# 12_-WIFI_Module_WF60.net
KiCad netlist of a schematic drawn in Altium Designer
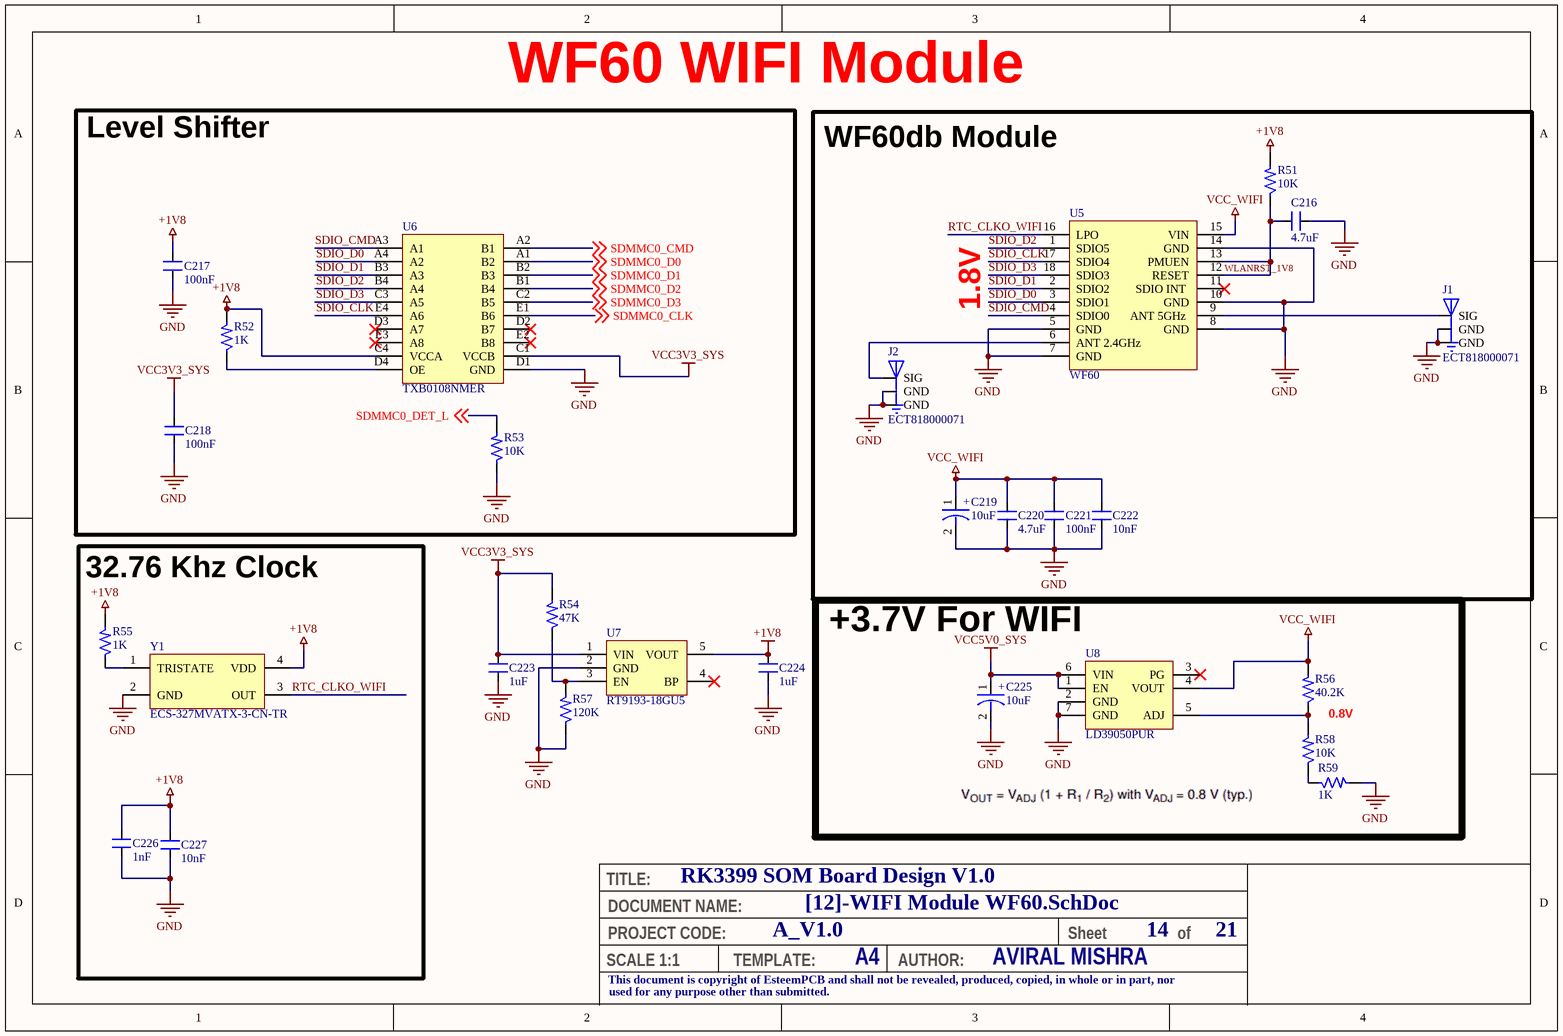
[diagram p0: [12]-WIFI Module WF60.SchDoc]

(export (version "E")
  (design (tool "Eeschema 10.0.6"))
  (components
    (comp (ref "C216")
      (value "4.7uF")
      (footprint "CAP_0402")
      (description "4.7µF ±10% 10V Ceramic Capacitor X5R 0402 (1005 Metric)")
      (fields
        (field (name "MANUFACTURER") "Samsung Electro-Mechanics")
        (field (name "MANUFACTURER PART NUMBER") "CL05A475KP5NRNC")
      )
      (libsource (lib "RK3399 _Module_Intlib") (part "CAP_4.7uF-10V-10%-0402"))
    )
    (comp (ref "C217")
      (value "100nF")
      (footprint "CAP_0402")
      (description "0.1µF ±10% 25V Ceramic Capacitor X7R 0402 (1005 Metric)")
      (fields
        (field (name "MANUFACTURER") "Walsin Technology Corporation")
        (field (name "MANUFACTURER PART NUMBER") "0402B104K250CT")
      )
      (libsource (lib "RK3399 _Module_Intlib") (part "CAP_100nF-25V-10%-0402"))
    )
    (comp (ref "C218")
      (value "100nF")
      (footprint "CAP_0402")
      (description "0.1µF ±10% 25V Ceramic Capacitor X7R 0402 (1005 Metric)")
      (fields
        (field (name "MANUFACTURER") "Walsin Technology Corporation")
        (field (name "MANUFACTURER PART NUMBER") "0402B104K250CT")
      )
      (libsource (lib "RK3399 _Module_Intlib") (part "CAP_100nF-25V-10%-0402"))
    )
    (comp (ref "C219")
      (value "10uF")
      (footprint "CAP-T_1206")
      (description "10µF Molded Tantalum Capacitors 16V 1206 (3216 Metric) 3Ohm")
      (fields
        (field (name "MANUFACTURER") "AVX Corporation")
        (field (name "MANUFACTURER PART NUMBER") "TAJA106K016SNJ")
      )
      (libsource (lib "RK3399 _Module_Intlib") (part "CAP-P_10uF-16V-10%-1206"))
    )
    (comp (ref "C220")
      (value "4.7uF")
      (footprint "CAP_0402")
      (description "4.7µF ±10% 10V Ceramic Capacitor X5R 0402 (1005 Metric)")
      (fields
        (field (name "MANUFACTURER") "Samsung Electro-Mechanics")
        (field (name "MANUFACTURER PART NUMBER") "CL05A475KP5NRNC")
      )
      (libsource (lib "RK3399 _Module_Intlib") (part "CAP_4.7uF-10V-10%-0402"))
    )
    (comp (ref "C221")
      (value "100nF")
      (footprint "CAP_0402")
      (description "0.1µF ±10% 25V Ceramic Capacitor X7R 0402 (1005 Metric)")
      (fields
        (field (name "MANUFACTURER") "Walsin Technology Corporation")
        (field (name "MANUFACTURER PART NUMBER") "0402B104K250CT")
      )
      (libsource (lib "RK3399 _Module_Intlib") (part "CAP_100nF-25V-10%-0402"))
    )
    (comp (ref "C222")
      (value "10nF")
      (footprint "CAP_0402")
      (description "10000pF ±10% 10V Ceramic Capacitor X7R 0402 (1005 Metric)")
      (fields
        (field (name "MANUFACTURER") "AVX Corporation")
        (field (name "MANUFACTURER PART NUMBER") "0402ZC103KAT2A")
      )
      (libsource (lib "RK3399 _Module_Intlib") (part "CAP_10nF-10V-10%-0402"))
    )
    (comp (ref "C223")
      (value "1uF")
      (footprint "CAP_0402")
      (description "1µF ±10% 16V Ceramic Capacitor X5R 0402 (1005 Metric)")
      (fields
        (field (name "MANUFACTURER") "Knowles Novacap")
        (field (name "MANUFACTURER PART NUMBER") "0402BW105K160YT")
      )
      (libsource (lib "RK3399 _Module_Schlib") (part "CAP_1uF-16V-10%-0402"))
    )
    (comp (ref "C224")
      (value "1uF")
      (footprint "CAP_0402")
      (description "1µF ±10% 16V Ceramic Capacitor X5R 0402 (1005 Metric)")
      (fields
        (field (name "MANUFACTURER") "Knowles Novacap")
        (field (name "MANUFACTURER PART NUMBER") "0402BW105K160YT")
      )
      (libsource (lib "RK3399 _Module_Schlib") (part "CAP_1uF-16V-10%-0402"))
    )
    (comp (ref "C225")
      (value "10uF")
      (footprint "CAP-T_1206")
      (description "10µF Molded Tantalum Capacitors 16V 1206 (3216 Metric) 3Ohm")
      (fields
        (field (name "MANUFACTURER") "AVX Corporation")
        (field (name "MANUFACTURER PART NUMBER") "TAJA106K016SNJ")
      )
      (libsource (lib "RK3399 _Module_Intlib") (part "CAP-P_10uF-16V-10%-1206"))
    )
    (comp (ref "C226")
      (value "1nF")
      (footprint "CAP_0402")
      (description "1000pF ±10% 16V Ceramic Capacitor X7R 0402 (1005 Metric)")
      (fields
        (field (name "MANUFACTURER") "Yageo")
        (field (name "MANUFACTURER PART NUMBER") "CC0402KRX7R7BB102")
      )
      (libsource (lib "RK3399 _Module_Intlib") (part "CAP_1nF-16V-10%-0402"))
    )
    (comp (ref "C227")
      (value "10nF")
      (footprint "CAP_0402")
      (description "10000pF ±10% 10V Ceramic Capacitor X7R 0402 (1005 Metric)")
      (fields
        (field (name "MANUFACTURER") "AVX Corporation")
        (field (name "MANUFACTURER PART NUMBER") "0402ZC103KAT2A")
      )
      (libsource (lib "RK3399 _Module_Intlib") (part "CAP_10nF-10V-10%-0402"))
    )
    (comp (ref "J1")
      (value "ECT818000071")
      (footprint "CON3_UFL_116_SMD_ST")
      (description "SMD RF Connectors/Coaxial Connectors RoHS")
      (fields (field (name "MANUFACTURER") "ECT"))
      (libsource (lib "RK3399 _Module_Intlib") (part "CON-PLG_3X1-ECT818000071-ST-SMD"))
    )
    (comp (ref "J2")
      (value "ECT818000071")
      (footprint "CON3_UFL_116_SMD_ST")
      (description "SMD RF Connectors/Coaxial Connectors RoHS")
      (fields (field (name "MANUFACTURER") "ECT"))
      (libsource (lib "RK3399 _Module_Intlib") (part "CON-PLG_3X1-ECT818000071-ST-SMD"))
    )
    (comp (ref "R51")
      (value "10K")
      (footprint "RES_0402")
      (description "10 kOhms ±1% 0.1W, 1/10W Chip Resistor 0402 (1005 Metric) Anti-Sulfur Thin Film")
      (fields
        (field (name "MANUFACTURER") "Vishay Beyschlag/Draloric/BC Components")
        (field (name "MANUFACTURER PART NUMBER") "MCS04020C1002FE000")
      )
      (libsource (lib "RK3399 _Module_Intlib") (part "RES_10K-0.1W-1%-0402"))
    )
    (comp (ref "R52")
      (value "1K")
      (footprint "RES_0402")
      (description "1 kOhms ±1% 0.1W, 1/10W Chip Resistor 0402 (1005 Metric) Anti-Sulfur Thin Film")
      (fields
        (field (name "MANUFACTURER") "Vishay Beyschlag/Draloric/BC Components")
        (field (name "MANUFACTURER PART NUMBER") "MCS04020C1001FE000")
      )
      (libsource (lib "RK3399 _Module_Intlib") (part "RES_1K-0.1W-1%-0402"))
    )
    (comp (ref "R53")
      (value "10K")
      (footprint "RES_0402")
      (description "10 kOhms ±1% 0.1W, 1/10W Chip Resistor 0402 (1005 Metric) Anti-Sulfur Thin Film")
      (fields
        (field (name "MANUFACTURER") "Vishay Beyschlag/Draloric/BC Components")
        (field (name "MANUFACTURER PART NUMBER") "MCS04020C1002FE000")
      )
      (libsource (lib "RK3399 _Module_Intlib") (part "RES_10K-0.1W-1%-0402"))
    )
    (comp (ref "R54")
      (value "47K")
      (footprint "RES_0402")
      (description "47 kOhms ±1% 0.1W, 1/10W Chip Resistor 0402 (1005 Metric) Automotive AEC-Q200 Thick Film")
      (fields
        (field (name "MANUFACTURER") "Panasonic Electronic Components")
        (field (name "MANUFACTURER PART NUMBER") "ERJ-2RKF4702X")
      )
      (libsource (lib "RK3399 _Module_Schlib") (part "RES_47K-0.1W-1%-0402"))
    )
    (comp (ref "R55")
      (value "1K")
      (footprint "RES_0402")
      (description "1 kOhms ±1% 0.1W, 1/10W Chip Resistor 0402 (1005 Metric) Anti-Sulfur Thin Film")
      (fields
        (field (name "MANUFACTURER") "Vishay Beyschlag/Draloric/BC Components")
        (field (name "MANUFACTURER PART NUMBER") "MCS04020C1001FE000")
      )
      (libsource (lib "RK3399 _Module_Intlib") (part "RES_1K-0.1W-1%-0402"))
    )
    (comp (ref "R56")
      (value "40.2K")
      (footprint "RES_0805")
      (description "40.2 kOhms ±1% 0.125W, 1/8W Chip Resistor 0805 (2012 Metric) Automotive AEC-Q200 Thick Film")
      (fields
        (field (name "MANUFACTURER") "TE Connectivity")
        (field (name "MANUFACTURER PART NUMBER") "RMCF0805FT40K2")
      )
      (libsource (lib "RK3399 _Module_Intlib") (part "RES_40.2K-0.125W-1%-0805"))
    )
    (comp (ref "R57")
      (value "120K")
      (footprint "RES_0402")
      (description "120 kOhms ±1% 0.1W, 1/10W Chip Resistor 0402 (1005 Metric) Anti-Sulfur Thin Film")
      (fields
        (field (name "MANUFACTURER") "Vishay Beyschlag/Draloric/BC Components")
        (field (name "MANUFACTURER PART NUMBER") "MCS04020C1203FE000")
      )
      (libsource (lib "RK3399 _Module_Schlib") (part "RES_120K-0.1W-1%-0402"))
    )
    (comp (ref "R58")
      (value "10K")
      (footprint "RES_0402")
      (description "10 kOhms ±1% 0.1W, 1/10W Chip Resistor 0402 (1005 Metric) Anti-Sulfur Thin Film")
      (fields
        (field (name "MANUFACTURER") "Vishay Beyschlag/Draloric/BC Components")
        (field (name "MANUFACTURER PART NUMBER") "MCS04020C1002FE000")
      )
      (libsource (lib "RK3399 _Module_Intlib") (part "RES_10K-0.1W-1%-0402"))
    )
    (comp (ref "R59")
      (value "1K")
      (footprint "RES_0402")
      (description "1 kOhms ±1% 0.1W, 1/10W Chip Resistor 0402 (1005 Metric) Anti-Sulfur Thin Film")
      (fields
        (field (name "MANUFACTURER") "Vishay Beyschlag/Draloric/BC Components")
        (field (name "MANUFACTURER PART NUMBER") "MCS04020C1001FE000")
      )
      (libsource (lib "RK3399 _Module_Intlib") (part "RES_1K-0.1W-1%-0402"))
    )
    (comp (ref "U5")
      (value "WF60")
      (footprint "MOD_WF60")
      (description "Amp’ed RF Tech presents the WF60 WiFi dual\r\nband module: 802.11abgn.")
      (fields (field (name "MANUFACTURER") "Amp’ed") (field (name "NYMBLE PART NUMBER") "1EA-AA-0568"))
      (libsource (lib "RK3399 _Module_Intlib") (part "MOD_WF60-SMD"))
    )
    (comp (ref "U6")
      (value "TXB0108NMER")
      (footprint "NFBGA_31.4_125.9X102.36")
      (fields (field (name "MANUFACTURER") "Texas Instruments"))
      (libsource (lib "RK3399 _Module_Intlib") (part "IC_TXB0108NMER"))
    )
    (comp (ref "U7")
      (value "RT9193-18GU5")
      (footprint "SC70-5")
      (description "Linear Voltage Regulator IC 1 Output 300mA SC-70-5")
      (fields (field (name "MANUFACTURER") "Richtek USA Inc."))
      (libsource (lib "RK3399 _Module_Schlib") (part "REG_1.8V-300mA-5.5V-SC70-5"))
    )
    (comp (ref "U8")
      (value "LD39050PUR")
      (footprint "DFN-6_37.4_165_33X15_SMD")
      (description "Adjustable 5.5V 0.8V 500mA DFN-6 Linear Voltage Regulators RoHS")
      (fields
        (field (name "MANUFACTURER") "STMicroelectronics")
        (field (name "NYMBLE PART NUMBER") "1EA-AA-0572")
      )
      (libsource (lib "RK3399 _Module_Intlib") (part "REG_5.5V-0~5.1V-0.5A-2.55W-DFN-6"))
    )
    (comp (ref "Y1")
      (value "ECS-327MVATX-3-CN-TR")
      (footprint "XTAL_57_35X31_SMD")
      (description "32.768kHz XO (Standard) CMOS Oscillator 1.6V ~ 3.6V Enable/Disable 4-SMD, No Lead")
      (fields (field (name "MANUFACTURER") "ECS INC") (field (name "NYMBLE PART NUMBER") "1EA-AA-0561"))
      (libsource (lib "RK3399 _Module_Intlib") (part "XTAL_ECS-327MVATX-2-CN-TR"))
    )
  )
  (nets
    (net (code "1") (name "+1V8") (class "Default")
      (node (ref "C217") (pin "2") (pinfunction "2_2") (pintype "passive"))
      (node (ref "C224") (pin "2") (pinfunction "2_2") (pintype "passive"))
      (node (ref "C226") (pin "2") (pinfunction "2_2") (pintype "passive"))
      (node (ref "C227") (pin "2") (pinfunction "2_2") (pintype "passive"))
      (node (ref "R51") (pin "2") (pinfunction "2_2") (pintype "passive"))
      (node (ref "R52") (pin "2") (pinfunction "2_2") (pintype "passive"))
      (node (ref "R55") (pin "2") (pinfunction "2_2") (pintype "passive"))
      (node (ref "U6") (pin "C4") (pinfunction "VCCA_C4") (pintype "passive"))
      (node (ref "U7") (pin "5") (pinfunction "VOUT_5") (pintype "passive"))
      (node (ref "Y1") (pin "4") (pinfunction "VDD_4") (pintype "passive"))
    )
    (net (code "2") (name "/RTC_CLKO_WIFI") (class "Default")
      (node (ref "U5") (pin "16") (pinfunction "LPO_16") (pintype "passive"))
      (node (ref "Y1") (pin "3") (pinfunction "OUT_3") (pintype "passive"))
    )
    (net (code "3") (name "/SDIO_CLK") (class "Default")
      (node (ref "U5") (pin "17") (pinfunction "SDIO4_17") (pintype "passive"))
      (node (ref "U6") (pin "E4") (pinfunction "A6_E4") (pintype "passive"))
    )
    (net (code "4") (name "/SDIO_CMD") (class "Default")
      (node (ref "U5") (pin "4") (pinfunction "SDIO0_4") (pintype "passive"))
      (node (ref "U6") (pin "A3") (pinfunction "A1_A3") (pintype "passive"))
    )
    (net (code "5") (name "/SDIO_D0") (class "Default")
      (node (ref "U5") (pin "3") (pinfunction "SDIO1_3") (pintype "passive"))
      (node (ref "U6") (pin "A4") (pinfunction "A2_A4") (pintype "passive"))
    )
    (net (code "6") (name "/SDIO_D1") (class "Default")
      (node (ref "U5") (pin "2") (pinfunction "SDIO2_2") (pintype "passive"))
      (node (ref "U6") (pin "B3") (pinfunction "A3_B3") (pintype "passive"))
    )
    (net (code "7") (name "/SDIO_D2") (class "Default")
      (node (ref "U5") (pin "1") (pinfunction "SDIO5_1") (pintype "passive"))
      (node (ref "U6") (pin "B4") (pinfunction "A4_B4") (pintype "passive"))
    )
    (net (code "8") (name "/SDIO_D3") (class "Default")
      (node (ref "U5") (pin "18") (pinfunction "SDIO3_18") (pintype "passive"))
      (node (ref "U6") (pin "C3") (pinfunction "A5_C3") (pintype "passive"))
    )
    (net (code "9") (name "/WLANRST_1V8") (class "Default")
      (node (ref "C216") (pin "2") (pinfunction "2_2") (pintype "passive"))
      (node (ref "R51") (pin "1") (pinfunction "1_1") (pintype "passive"))
      (node (ref "U5") (pin "12") (pinfunction "RESET_12") (pintype "passive"))
      (node (ref "U5") (pin "13") (pinfunction "PMUEN_13") (pintype "passive"))
    )
    (net (code "10") (name "GND") (class "Default")
      (node (ref "C216") (pin "1") (pinfunction "1_1") (pintype "passive"))
      (node (ref "C217") (pin "1") (pinfunction "1_1") (pintype "passive"))
      (node (ref "C218") (pin "1") (pinfunction "1_1") (pintype "passive"))
      (node (ref "C219") (pin "2") (pinfunction "2_2") (pintype "passive"))
      (node (ref "C220") (pin "1") (pinfunction "1_1") (pintype "passive"))
      (node (ref "C221") (pin "1") (pinfunction "1_1") (pintype "passive"))
      (node (ref "C222") (pin "1") (pinfunction "1_1") (pintype "passive"))
      (node (ref "C223") (pin "1") (pinfunction "1_1") (pintype "passive"))
      (node (ref "C224") (pin "1") (pinfunction "1_1") (pintype "passive"))
      (node (ref "C225") (pin "2") (pinfunction "2_2") (pintype "passive"))
      (node (ref "C226") (pin "1") (pinfunction "1_1") (pintype "passive"))
      (node (ref "C227") (pin "1") (pinfunction "1_1") (pintype "passive"))
      (node (ref "J1") (pin "1") (pinfunction "GND_1") (pintype "passive"))
      (node (ref "J1") (pin "3") (pinfunction "GND_3") (pintype "passive"))
      (node (ref "J2") (pin "1") (pinfunction "GND_1") (pintype "passive"))
      (node (ref "J2") (pin "3") (pinfunction "GND_3") (pintype "passive"))
      (node (ref "R53") (pin "1") (pinfunction "1_1") (pintype "passive"))
      (node (ref "R57") (pin "1") (pinfunction "1_1") (pintype "passive"))
      (node (ref "R59") (pin "2") (pinfunction "2_2") (pintype "passive"))
      (node (ref "U5") (pin "10") (pinfunction "GND_10") (pintype "passive"))
      (node (ref "U5") (pin "14") (pinfunction "GND_14") (pintype "passive"))
      (node (ref "U5") (pin "5") (pinfunction "GND_5") (pintype "passive"))
      (node (ref "U5") (pin "7") (pinfunction "GND_7") (pintype "passive"))
      (node (ref "U5") (pin "8") (pinfunction "GND_8") (pintype "passive"))
      (node (ref "U6") (pin "D1") (pinfunction "GND_D1") (pintype "passive"))
      (node (ref "U7") (pin "2") (pinfunction "GND_2") (pintype "passive"))
      (node (ref "U8") (pin "2") (pinfunction "GND_2") (pintype "passive"))
      (node (ref "U8") (pin "7") (pinfunction "GND_7") (pintype "passive"))
      (node (ref "Y1") (pin "2") (pinfunction "GND_2") (pintype "passive"))
    )
    (net (code "11") (name "Net-(J1-SIG)") (class "Default")
      (node (ref "J1") (pin "2") (pinfunction "SIG_2") (pintype "passive"))
      (node (ref "U5") (pin "9") (pinfunction "ANT_5GHz_9") (pintype "passive"))
    )
    (net (code "12") (name "Net-(J2-SIG)") (class "Default")
      (node (ref "J2") (pin "2") (pinfunction "SIG_2") (pintype "passive"))
      (node (ref "U5") (pin "6") (pinfunction "ANT_2.4GHz_6") (pintype "passive"))
    )
    (net (code "13") (name "Net-(R58-Pad1)") (class "Default")
      (node (ref "R58") (pin "1") (pinfunction "1_1") (pintype "passive"))
      (node (ref "R59") (pin "1") (pinfunction "1_1") (pintype "passive"))
    )
    (net (code "14") (name "Net-(U6-OE)") (class "Default")
      (node (ref "R52") (pin "1") (pinfunction "1_1") (pintype "passive"))
      (node (ref "U6") (pin "D4") (pinfunction "OE_D4") (pintype "passive"))
    )
    (net (code "15") (name "Net-(U7-EN)") (class "Default")
      (node (ref "R54") (pin "1") (pinfunction "1_1") (pintype "passive"))
      (node (ref "R57") (pin "2") (pinfunction "2_2") (pintype "passive"))
      (node (ref "U7") (pin "3") (pinfunction "EN_3") (pintype "passive"))
    )
    (net (code "16") (name "Net-(U8-ADJ)") (class "Default")
      (node (ref "R56") (pin "1") (pinfunction "1_1") (pintype "passive"))
      (node (ref "R58") (pin "2") (pinfunction "2_2") (pintype "passive"))
      (node (ref "U8") (pin "5") (pinfunction "ADJ_5") (pintype "passive"))
    )
    (net (code "17") (name "Net-(Y1-TRISTATE)") (class "Default")
      (node (ref "R55") (pin "1") (pinfunction "1_1") (pintype "passive"))
      (node (ref "Y1") (pin "1") (pinfunction "TRISTATE_1") (pintype "passive"))
    )
    (net (code "18") (name "SDMMC0_CLK") (class "Default")
      (node (ref "U6") (pin "E1") (pinfunction "B6_E1") (pintype "passive"))
    )
    (net (code "19") (name "SDMMC0_CMD") (class "Default")
      (node (ref "U6") (pin "A2") (pinfunction "B1_A2") (pintype "passive"))
    )
    (net (code "20") (name "SDMMC0_D0") (class "Default")
      (node (ref "U6") (pin "A1") (pinfunction "B2_A1") (pintype "passive"))
    )
    (net (code "21") (name "SDMMC0_D1") (class "Default")
      (node (ref "U6") (pin "B2") (pinfunction "B3_B2") (pintype "passive"))
    )
    (net (code "22") (name "SDMMC0_D2") (class "Default")
      (node (ref "U6") (pin "B1") (pinfunction "B4_B1") (pintype "passive"))
    )
    (net (code "23") (name "SDMMC0_D3") (class "Default")
      (node (ref "U6") (pin "C2") (pinfunction "B5_C2") (pintype "passive"))
    )
    (net (code "24") (name "SDMMC0_DET_L") (class "Default")
      (node (ref "R53") (pin "2") (pinfunction "2_2") (pintype "passive"))
    )
    (net (code "25") (name "VCC3V3_SYS") (class "Default")
      (node (ref "C218") (pin "2") (pinfunction "2_2") (pintype "passive"))
      (node (ref "C223") (pin "2") (pinfunction "2_2") (pintype "passive"))
      (node (ref "R54") (pin "2") (pinfunction "2_2") (pintype "passive"))
      (node (ref "U6") (pin "C1") (pinfunction "VCCB_C1") (pintype "passive"))
      (node (ref "U7") (pin "1") (pinfunction "VIN_1") (pintype "passive"))
    )
    (net (code "26") (name "VCC5V0_SYS") (class "Default")
      (node (ref "C225") (pin "1") (pinfunction "1_1") (pintype "passive"))
      (node (ref "U8") (pin "1") (pinfunction "EN_1") (pintype "passive"))
      (node (ref "U8") (pin "6") (pinfunction "VIN_6") (pintype "passive"))
    )
    (net (code "27") (name "VCC_WIFI") (class "Default")
      (node (ref "C219") (pin "1") (pinfunction "1_1") (pintype "passive"))
      (node (ref "C220") (pin "2") (pinfunction "2_2") (pintype "passive"))
      (node (ref "C221") (pin "2") (pinfunction "2_2") (pintype "passive"))
      (node (ref "C222") (pin "2") (pinfunction "2_2") (pintype "passive"))
      (node (ref "R56") (pin "2") (pinfunction "2_2") (pintype "passive"))
      (node (ref "U5") (pin "15") (pinfunction "VIN_15") (pintype "passive"))
      (node (ref "U8") (pin "4") (pinfunction "VOUT_4") (pintype "passive"))
    )
    (net (code "28") (name "unconnected-(U5-SDIO_INT-Pad11)") (class "Default")
      (node (ref "U5") (pin "11") (pinfunction "SDIO_INT_11") (pintype "passive+no_connect"))
    )
    (net (code "29") (name "unconnected-(U6-A7-PadD3)") (class "Default")
      (node (ref "U6") (pin "D3") (pinfunction "A7_D3") (pintype "passive+no_connect"))
    )
    (net (code "30") (name "unconnected-(U6-A8-PadE3)") (class "Default")
      (node (ref "U6") (pin "E3") (pinfunction "A8_E3") (pintype "passive+no_connect"))
    )
    (net (code "31") (name "unconnected-(U6-B7-PadD2)") (class "Default")
      (node (ref "U6") (pin "D2") (pinfunction "B7_D2") (pintype "passive+no_connect"))
    )
    (net (code "32") (name "unconnected-(U6-B8-PadE2)") (class "Default")
      (node (ref "U6") (pin "E2") (pinfunction "B8_E2") (pintype "passive+no_connect"))
    )
    (net (code "33") (name "unconnected-(U7-BP-Pad4)") (class "Default")
      (node (ref "U7") (pin "4") (pinfunction "BP_4") (pintype "passive+no_connect"))
    )
    (net (code "34") (name "unconnected-(U8-PG-Pad3)") (class "Default")
      (node (ref "U8") (pin "3") (pinfunction "PG_3") (pintype "passive+no_connect"))
    )
  )
)
